# R3Change_1.net
KiCad netlist of a schematic drawn in Altium Designer
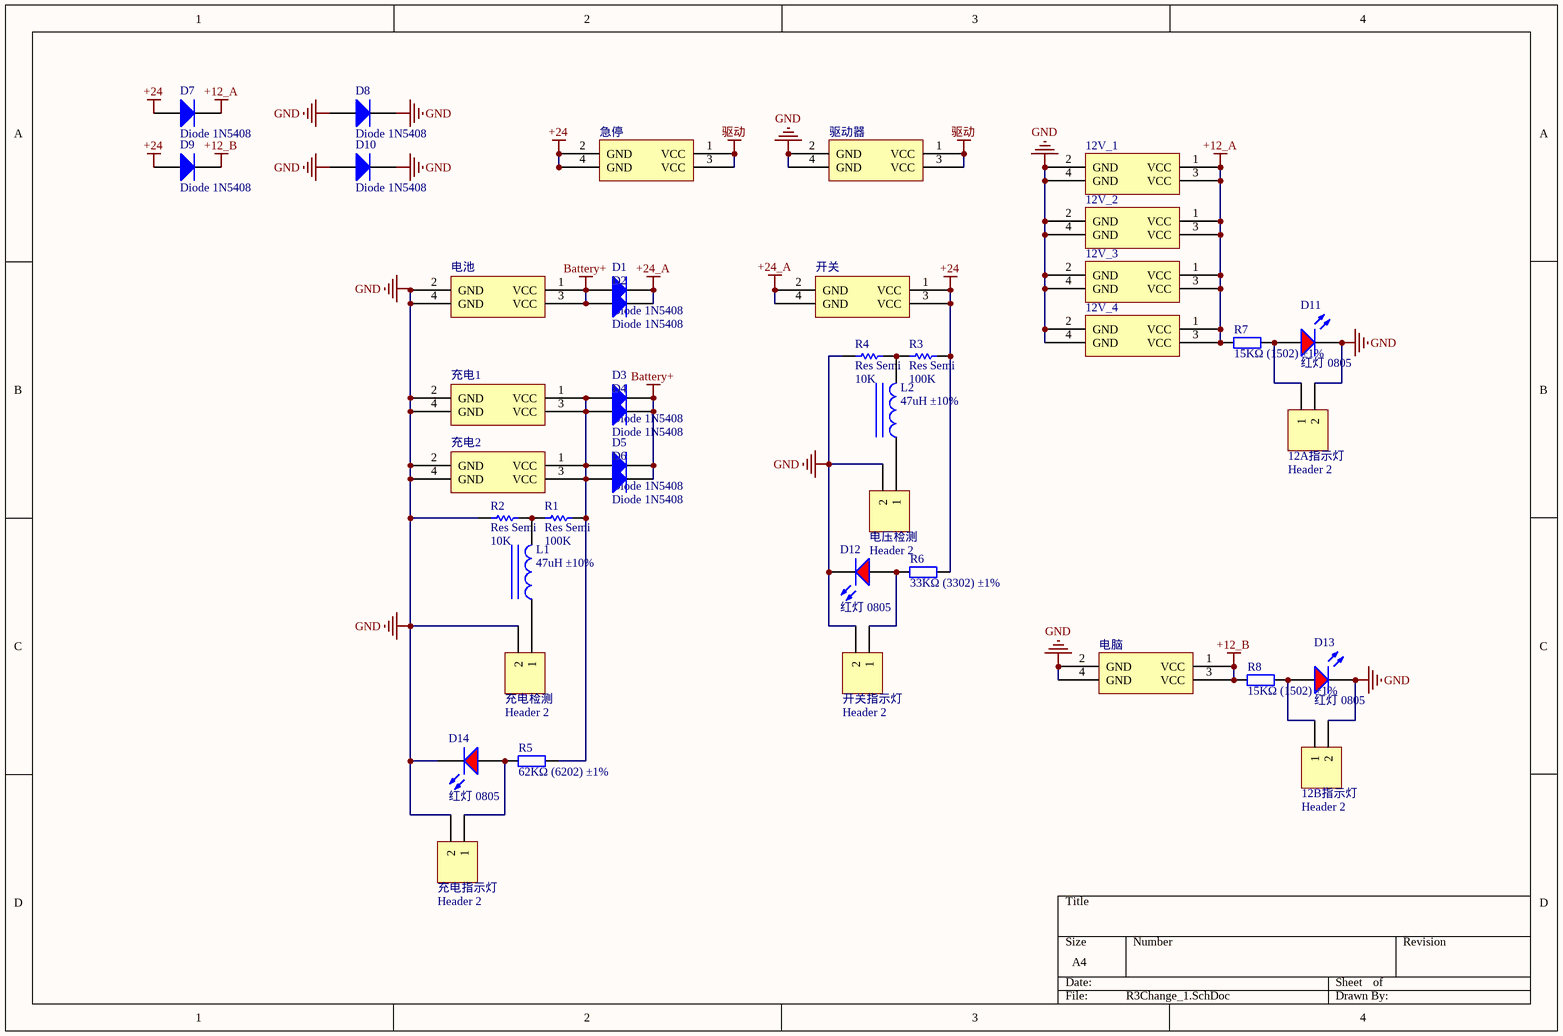
[diagram p0: R3Change_1.SchDoc]

(export (version "E")
  (design (tool "Eeschema 10.0.6"))
  (components
    (comp (ref "12A指示灯")
      (value "Header 2")
      (footprint "HDR1X2")
      (description "Header, 2-Pin")
      (fields (field (name "PUBLISHER") "Altium Limited"))
      (libsource (lib "Miscellaneous Connectors") (part "Header 2"))
    )
    (comp (ref "12B指示灯")
      (value "Header 2")
      (footprint "HDR1X2")
      (description "Header, 2-Pin")
      (fields (field (name "PUBLISHER") "Altium Limited"))
      (libsource (lib "Miscellaneous Connectors") (part "Header 2"))
    )
    (comp (ref "12V_1")
      (value "插座")
      (footprint "HEADER 2X2")
      (libsource (lib "AD_Chip_Y") (part "HEADER_2X2"))
    )
    (comp (ref "12V_2")
      (value "插座")
      (footprint "HEADER 2X2")
      (libsource (lib "AD_Chip_Y") (part "HEADER_2X2"))
    )
    (comp (ref "12V_3")
      (value "插座")
      (footprint "HEADER 2X2")
      (libsource (lib "AD_Chip_Y") (part "HEADER_2X2"))
    )
    (comp (ref "12V_4")
      (value "插座")
      (footprint "HEADER 2X2")
      (libsource (lib "AD_Chip_Y") (part "HEADER_2X2"))
    )
    (comp (ref "D1")
      (value "Diode 1N5408")
      (footprint "DO-201AD")
      (description "3 Amp Medium Power Silicon Rectifier Diode")
      (fields (field (name "PUBLISHER") "Altium Limited"))
      (libsource (lib "Miscellaneous Devices") (part "Diode 1N5408"))
    )
    (comp (ref "D2")
      (value "Diode 1N5408")
      (footprint "DO-201AD")
      (description "3 Amp Medium Power Silicon Rectifier Diode")
      (fields (field (name "PUBLISHER") "Altium Limited"))
      (libsource (lib "Miscellaneous Devices") (part "Diode 1N5408"))
    )
    (comp (ref "D3")
      (value "Diode 1N5408")
      (footprint "DO-201AD")
      (description "3 Amp Medium Power Silicon Rectifier Diode")
      (fields (field (name "PUBLISHER") "Altium Limited"))
      (libsource (lib "Miscellaneous Devices") (part "Diode 1N5408"))
    )
    (comp (ref "D4")
      (value "Diode 1N5408")
      (footprint "DO-201AD")
      (description "3 Amp Medium Power Silicon Rectifier Diode")
      (fields (field (name "PUBLISHER") "Altium Limited"))
      (libsource (lib "Miscellaneous Devices") (part "Diode 1N5408"))
    )
    (comp (ref "D5")
      (value "Diode 1N5408")
      (footprint "DO-201AD")
      (description "3 Amp Medium Power Silicon Rectifier Diode")
      (fields (field (name "PUBLISHER") "Altium Limited"))
      (libsource (lib "Miscellaneous Devices") (part "Diode 1N5408"))
    )
    (comp (ref "D6")
      (value "Diode 1N5408")
      (footprint "DO-201AD")
      (description "3 Amp Medium Power Silicon Rectifier Diode")
      (fields (field (name "PUBLISHER") "Altium Limited"))
      (libsource (lib "Miscellaneous Devices") (part "Diode 1N5408"))
    )
    (comp (ref "D7")
      (value "Diode 1N5408")
      (footprint "DO-201AD")
      (description "3 Amp Medium Power Silicon Rectifier Diode")
      (fields (field (name "PUBLISHER") "Altium Limited"))
      (libsource (lib "Miscellaneous Devices") (part "Diode 1N5408"))
    )
    (comp (ref "D8")
      (value "Diode 1N5408")
      (footprint "DO-201AD")
      (description "3 Amp Medium Power Silicon Rectifier Diode")
      (fields (field (name "PUBLISHER") "Altium Limited"))
      (libsource (lib "Miscellaneous Devices") (part "Diode 1N5408"))
    )
    (comp (ref "D9")
      (value "Diode 1N5408")
      (footprint "DO-201AD")
      (description "3 Amp Medium Power Silicon Rectifier Diode")
      (fields (field (name "PUBLISHER") "Altium Limited"))
      (libsource (lib "Miscellaneous Devices") (part "Diode 1N5408"))
    )
    (comp (ref "D10")
      (value "Diode 1N5408")
      (footprint "DO-201AD")
      (description "3 Amp Medium Power Silicon Rectifier Diode")
      (fields (field (name "PUBLISHER") "Altium Limited"))
      (libsource (lib "Miscellaneous Devices") (part "Diode 1N5408"))
    )
    (comp (ref "D11")
      (value "红灯 0805")
      (footprint "LC-0805_LED_S1")
      (description "发光二极管")
      (libsource (lib "Miscellaneous Devices LC") (part "0805 红灯"))
    )
    (comp (ref "D12")
      (value "红灯 0805")
      (footprint "LC-0805_LED_S1")
      (description "发光二极管")
      (libsource (lib "Miscellaneous Devices LC") (part "0805 红灯"))
    )
    (comp (ref "D13")
      (value "红灯 0805")
      (footprint "LC-0805_LED_S1")
      (description "发光二极管")
      (libsource (lib "Miscellaneous Devices LC") (part "0805 红灯"))
    )
    (comp (ref "D14")
      (value "红灯 0805")
      (footprint "LC-0805_LED_S1")
      (description "发光二极管")
      (libsource (lib "Miscellaneous Devices LC") (part "0805 红灯"))
    )
    (comp (ref "L1")
      (value "47uH ±10%")
      (footprint "LC-0805_L")
      (description "贴片电感")
      (libsource (lib "Miscellaneous Devices LC") (part "0805 47uH 10%"))
    )
    (comp (ref "L2")
      (value "47uH ±10%")
      (footprint "LC-0805_L")
      (description "贴片电感")
      (libsource (lib "Miscellaneous Devices LC") (part "0805 47uH 10%"))
    )
    (comp (ref "R1")
      (value "Res Semi")
      (footprint "AXIAL-0.5")
      (description "Semiconductor Resistor")
      (fields (field (name "ALTIUM_VALUE") "100K") (field (name "PUBLISHER") "Altium Limited"))
      (libsource (lib "Miscellaneous Devices") (part "Res Semi"))
    )
    (comp (ref "R2")
      (value "Res Semi")
      (footprint "AXIAL-0.5")
      (description "Semiconductor Resistor")
      (fields (field (name "ALTIUM_VALUE") "10K") (field (name "PUBLISHER") "Altium Limited"))
      (libsource (lib "Miscellaneous Devices") (part "Res Semi"))
    )
    (comp (ref "R3")
      (value "Res Semi")
      (footprint "AXIAL-0.5")
      (description "Semiconductor Resistor")
      (fields (field (name "ALTIUM_VALUE") "100K") (field (name "PUBLISHER") "Altium Limited"))
      (libsource (lib "Miscellaneous Devices") (part "Res Semi"))
    )
    (comp (ref "R4")
      (value "Res Semi")
      (footprint "AXIAL-0.5")
      (description "Semiconductor Resistor")
      (fields (field (name "ALTIUM_VALUE") "10K") (field (name "PUBLISHER") "Altium Limited"))
      (libsource (lib "Miscellaneous Devices") (part "Res Semi"))
    )
    (comp (ref "R5")
      (value "62KΩ (6202) ±1%")
      (footprint "LC-0805_R")
      (description "贴片电阻")
      (libsource (lib "Miscellaneous Devices LC") (part "0805 62KΩ (6202) 1%"))
    )
    (comp (ref "R6")
      (value "33KΩ (3302) ±1%")
      (footprint "LC-0805_R")
      (description "贴片电阻")
      (libsource (lib "Miscellaneous Devices LC") (part "0805 33KΩ (3302) 1%"))
    )
    (comp (ref "R7")
      (value "15KΩ (1502) ±1%")
      (footprint "LC-0805_R")
      (description "贴片电阻")
      (libsource (lib "Miscellaneous Devices LC") (part "0805 15KΩ (1502) 1%"))
    )
    (comp (ref "R8")
      (value "15KΩ (1502) ±1%")
      (footprint "LC-0805_R")
      (description "贴片电阻")
      (libsource (lib "Miscellaneous Devices LC") (part "0805 15KΩ (1502) 1%"))
    )
    (comp (ref "充电1") (value "插座") (footprint "HEADER 2X2") (libsource (lib "AD_Chip_Y") (part "HEADER_2X2")))
    (comp (ref "充电2") (value "插座") (footprint "HEADER 2X2") (libsource (lib "AD_Chip_Y") (part "HEADER_2X2")))
    (comp (ref "充电指示灯")
      (value "Header 2")
      (footprint "HDR1X2")
      (description "Header, 2-Pin")
      (fields (field (name "PUBLISHER") "Altium Limited"))
      (libsource (lib "") (part "Header 2_1"))
    )
    (comp (ref "充电检测")
      (value "Header 2")
      (footprint "HDR1X2")
      (description "Header, 2-Pin")
      (fields (field (name "PUBLISHER") "Altium Limited"))
      (libsource (lib "") (part "Header 2_1"))
    )
    (comp (ref "开关") (value "插座") (footprint "HEADER 2X2") (libsource (lib "AD_Chip_Y") (part "HEADER_2X2")))
    (comp (ref "开关指示灯")
      (value "Header 2")
      (footprint "HDR1X2")
      (description "Header, 2-Pin")
      (fields (field (name "PUBLISHER") "Altium Limited"))
      (libsource (lib "") (part "Header 2_1"))
    )
    (comp (ref "急停") (value "插座") (footprint "HEADER 2X2") (libsource (lib "AD_Chip_Y") (part "HEADER_2X2")))
    (comp (ref "电压检测")
      (value "Header 2")
      (footprint "HDR1X2")
      (description "Header, 2-Pin")
      (fields (field (name "PUBLISHER") "Altium Limited"))
      (libsource (lib "") (part "Header 2_1"))
    )
    (comp (ref "电池") (value "插座") (footprint "HEADER 2X2") (libsource (lib "AD_Chip_Y") (part "HEADER_2X2")))
    (comp (ref "电脑") (value "插座") (footprint "HEADER 2X2") (libsource (lib "AD_Chip_Y") (part "HEADER_2X2")))
    (comp (ref "驱动器") (value "插座") (footprint "HEADER 2X2") (libsource (lib "AD_Chip_Y") (part "HEADER_2X2")))
  )
  (nets
    (net (code "1") (name "+12_A") (class "Default")
      (node (ref "12V_1") (pin "1") (pinfunction "VCC_1") (pintype "passive"))
      (node (ref "12V_1") (pin "3") (pinfunction "VCC_3") (pintype "passive"))
      (node (ref "12V_2") (pin "1") (pinfunction "VCC_1") (pintype "passive"))
      (node (ref "12V_2") (pin "3") (pinfunction "VCC_3") (pintype "passive"))
      (node (ref "12V_3") (pin "1") (pinfunction "VCC_1") (pintype "passive"))
      (node (ref "12V_3") (pin "3") (pinfunction "VCC_3") (pintype "passive"))
      (node (ref "12V_4") (pin "1") (pinfunction "VCC_1") (pintype "passive"))
      (node (ref "12V_4") (pin "3") (pinfunction "VCC_3") (pintype "passive"))
      (node (ref "D7") (pin "2") (pinfunction "K_2") (pintype "passive"))
      (node (ref "R7") (pin "1") (pinfunction "1_1") (pintype "passive"))
    )
    (net (code "2") (name "+12_B") (class "Default")
      (node (ref "D9") (pin "2") (pinfunction "K_2") (pintype "passive"))
      (node (ref "R8") (pin "1") (pinfunction "1_1") (pintype "passive"))
      (node (ref "电脑") (pin "1") (pinfunction "VCC_1") (pintype "passive"))
      (node (ref "电脑") (pin "3") (pinfunction "VCC_3") (pintype "passive"))
    )
    (net (code "3") (name "+24") (class "Default")
      (node (ref "D7") (pin "1") (pinfunction "A_1") (pintype "passive"))
      (node (ref "D9") (pin "1") (pinfunction "A_1") (pintype "passive"))
      (node (ref "R3") (pin "2") (pinfunction "2_2") (pintype "passive"))
      (node (ref "R6") (pin "2") (pinfunction "2_2") (pintype "passive"))
      (node (ref "开关") (pin "1") (pinfunction "VCC_1") (pintype "passive"))
      (node (ref "开关") (pin "3") (pinfunction "VCC_3") (pintype "passive"))
      (node (ref "急停") (pin "2") (pinfunction "GND_2") (pintype "passive"))
      (node (ref "急停") (pin "4") (pinfunction "GND_4") (pintype "passive"))
    )
    (net (code "4") (name "+24_A") (class "Default")
      (node (ref "D1") (pin "2") (pinfunction "K_2") (pintype "passive"))
      (node (ref "D2") (pin "2") (pinfunction "K_2") (pintype "passive"))
      (node (ref "开关") (pin "2") (pinfunction "GND_2") (pintype "passive"))
      (node (ref "开关") (pin "4") (pinfunction "GND_4") (pintype "passive"))
    )
    (net (code "5") (name "Battery+") (class "Default")
      (node (ref "D1") (pin "1") (pinfunction "A_1") (pintype "passive"))
      (node (ref "D2") (pin "1") (pinfunction "A_1") (pintype "passive"))
      (node (ref "D3") (pin "2") (pinfunction "K_2") (pintype "passive"))
      (node (ref "D4") (pin "2") (pinfunction "K_2") (pintype "passive"))
      (node (ref "D5") (pin "2") (pinfunction "K_2") (pintype "passive"))
      (node (ref "D6") (pin "2") (pinfunction "K_2") (pintype "passive"))
      (node (ref "电池") (pin "1") (pinfunction "VCC_1") (pintype "passive"))
      (node (ref "电池") (pin "3") (pinfunction "VCC_3") (pintype "passive"))
    )
    (net (code "6") (name "GND") (class "Default")
      (node (ref "12A指示灯") (pin "2") (pinfunction "2_2") (pintype "passive"))
      (node (ref "12B指示灯") (pin "2") (pinfunction "2_2") (pintype "passive"))
      (node (ref "12V_1") (pin "2") (pinfunction "GND_2") (pintype "passive"))
      (node (ref "12V_1") (pin "4") (pinfunction "GND_4") (pintype "passive"))
      (node (ref "12V_2") (pin "2") (pinfunction "GND_2") (pintype "passive"))
      (node (ref "12V_2") (pin "4") (pinfunction "GND_4") (pintype "passive"))
      (node (ref "12V_3") (pin "2") (pinfunction "GND_2") (pintype "passive"))
      (node (ref "12V_3") (pin "4") (pinfunction "GND_4") (pintype "passive"))
      (node (ref "12V_4") (pin "2") (pinfunction "GND_2") (pintype "passive"))
      (node (ref "12V_4") (pin "4") (pinfunction "GND_4") (pintype "passive"))
      (node (ref "D10") (pin "1") (pinfunction "A_1") (pintype "passive"))
      (node (ref "D10") (pin "2") (pinfunction "K_2") (pintype "passive"))
      (node (ref "D11") (pin "K") (pinfunction "K_K") (pintype "passive"))
      (node (ref "D12") (pin "K") (pinfunction "K_K") (pintype "passive"))
      (node (ref "D13") (pin "K") (pinfunction "K_K") (pintype "passive"))
      (node (ref "D14") (pin "K") (pinfunction "K_K") (pintype "passive"))
      (node (ref "D8") (pin "1") (pinfunction "A_1") (pintype "passive"))
      (node (ref "D8") (pin "2") (pinfunction "K_2") (pintype "passive"))
      (node (ref "R2") (pin "1") (pinfunction "1_1") (pintype "passive"))
      (node (ref "R4") (pin "1") (pinfunction "1_1") (pintype "passive"))
      (node (ref "充电1") (pin "2") (pinfunction "GND_2") (pintype "passive"))
      (node (ref "充电1") (pin "4") (pinfunction "GND_4") (pintype "passive"))
      (node (ref "充电2") (pin "2") (pinfunction "GND_2") (pintype "passive"))
      (node (ref "充电2") (pin "4") (pinfunction "GND_4") (pintype "passive"))
      (node (ref "充电指示灯") (pin "2") (pinfunction "2_2") (pintype "passive"))
      (node (ref "充电检测") (pin "2") (pinfunction "2_2") (pintype "passive"))
      (node (ref "开关指示灯") (pin "2") (pinfunction "2_2") (pintype "passive"))
      (node (ref "电压检测") (pin "2") (pinfunction "2_2") (pintype "passive"))
      (node (ref "电池") (pin "2") (pinfunction "GND_2") (pintype "passive"))
      (node (ref "电池") (pin "4") (pinfunction "GND_4") (pintype "passive"))
      (node (ref "电脑") (pin "2") (pinfunction "GND_2") (pintype "passive"))
      (node (ref "电脑") (pin "4") (pinfunction "GND_4") (pintype "passive"))
      (node (ref "驱动器") (pin "2") (pinfunction "GND_2") (pintype "passive"))
      (node (ref "驱动器") (pin "4") (pinfunction "GND_4") (pintype "passive"))
    )
    (net (code "7") (name "Net-(12A指示灯-Pad1)") (class "Default")
      (node (ref "12A指示灯") (pin "1") (pinfunction "1_1") (pintype "passive"))
      (node (ref "D11") (pin "A") (pinfunction "A_A") (pintype "passive"))
      (node (ref "R7") (pin "2") (pinfunction "2_2") (pintype "passive"))
    )
    (net (code "8") (name "Net-(12B指示灯-Pad1)") (class "Default")
      (node (ref "12B指示灯") (pin "1") (pinfunction "1_1") (pintype "passive"))
      (node (ref "D13") (pin "A") (pinfunction "A_A") (pintype "passive"))
      (node (ref "R8") (pin "2") (pinfunction "2_2") (pintype "passive"))
    )
    (net (code "9") (name "Net-(D3-A)") (class "Default")
      (node (ref "D3") (pin "1") (pinfunction "A_1") (pintype "passive"))
      (node (ref "D4") (pin "1") (pinfunction "A_1") (pintype "passive"))
      (node (ref "D5") (pin "1") (pinfunction "A_1") (pintype "passive"))
      (node (ref "D6") (pin "1") (pinfunction "A_1") (pintype "passive"))
      (node (ref "R1") (pin "2") (pinfunction "2_2") (pintype "passive"))
      (node (ref "R5") (pin "2") (pinfunction "2_2") (pintype "passive"))
      (node (ref "充电1") (pin "1") (pinfunction "VCC_1") (pintype "passive"))
      (node (ref "充电1") (pin "3") (pinfunction "VCC_3") (pintype "passive"))
      (node (ref "充电2") (pin "1") (pinfunction "VCC_1") (pintype "passive"))
      (node (ref "充电2") (pin "3") (pinfunction "VCC_3") (pintype "passive"))
    )
    (net (code "10") (name "Net-(D12-PadA)") (class "Default")
      (node (ref "D12") (pin "A") (pinfunction "A_A") (pintype "passive"))
      (node (ref "R6") (pin "1") (pinfunction "1_1") (pintype "passive"))
      (node (ref "开关指示灯") (pin "1") (pinfunction "1_1") (pintype "passive"))
    )
    (net (code "11") (name "Net-(D14-PadA)") (class "Default")
      (node (ref "D14") (pin "A") (pinfunction "A_A") (pintype "passive"))
      (node (ref "R5") (pin "1") (pinfunction "1_1") (pintype "passive"))
      (node (ref "充电指示灯") (pin "1") (pinfunction "1_1") (pintype "passive"))
    )
    (net (code "12") (name "Net-(L1-Pad1)") (class "Default")
      (node (ref "L1") (pin "1") (pinfunction "1_1") (pintype "passive"))
      (node (ref "充电检测") (pin "1") (pinfunction "1_1") (pintype "passive"))
    )
    (net (code "13") (name "Net-(L1-Pad2)") (class "Default")
      (node (ref "L1") (pin "2") (pinfunction "2_2") (pintype "passive"))
      (node (ref "R1") (pin "1") (pinfunction "1_1") (pintype "passive"))
      (node (ref "R2") (pin "2") (pinfunction "2_2") (pintype "passive"))
    )
    (net (code "14") (name "Net-(L2-Pad1)") (class "Default")
      (node (ref "L2") (pin "1") (pinfunction "1_1") (pintype "passive"))
      (node (ref "电压检测") (pin "1") (pinfunction "1_1") (pintype "passive"))
    )
    (net (code "15") (name "Net-(L2-Pad2)") (class "Default")
      (node (ref "L2") (pin "2") (pinfunction "2_2") (pintype "passive"))
      (node (ref "R3") (pin "1") (pinfunction "1_1") (pintype "passive"))
      (node (ref "R4") (pin "2") (pinfunction "2_2") (pintype "passive"))
    )
    (net (code "16") (name "驱动") (class "Default")
      (node (ref "急停") (pin "1") (pinfunction "VCC_1") (pintype "passive"))
      (node (ref "急停") (pin "3") (pinfunction "VCC_3") (pintype "passive"))
      (node (ref "驱动器") (pin "1") (pinfunction "VCC_1") (pintype "passive"))
      (node (ref "驱动器") (pin "3") (pinfunction "VCC_3") (pintype "passive"))
    )
  )
)
